# PAGE2.net
KiCad netlist of a schematic drawn in Altium Designer
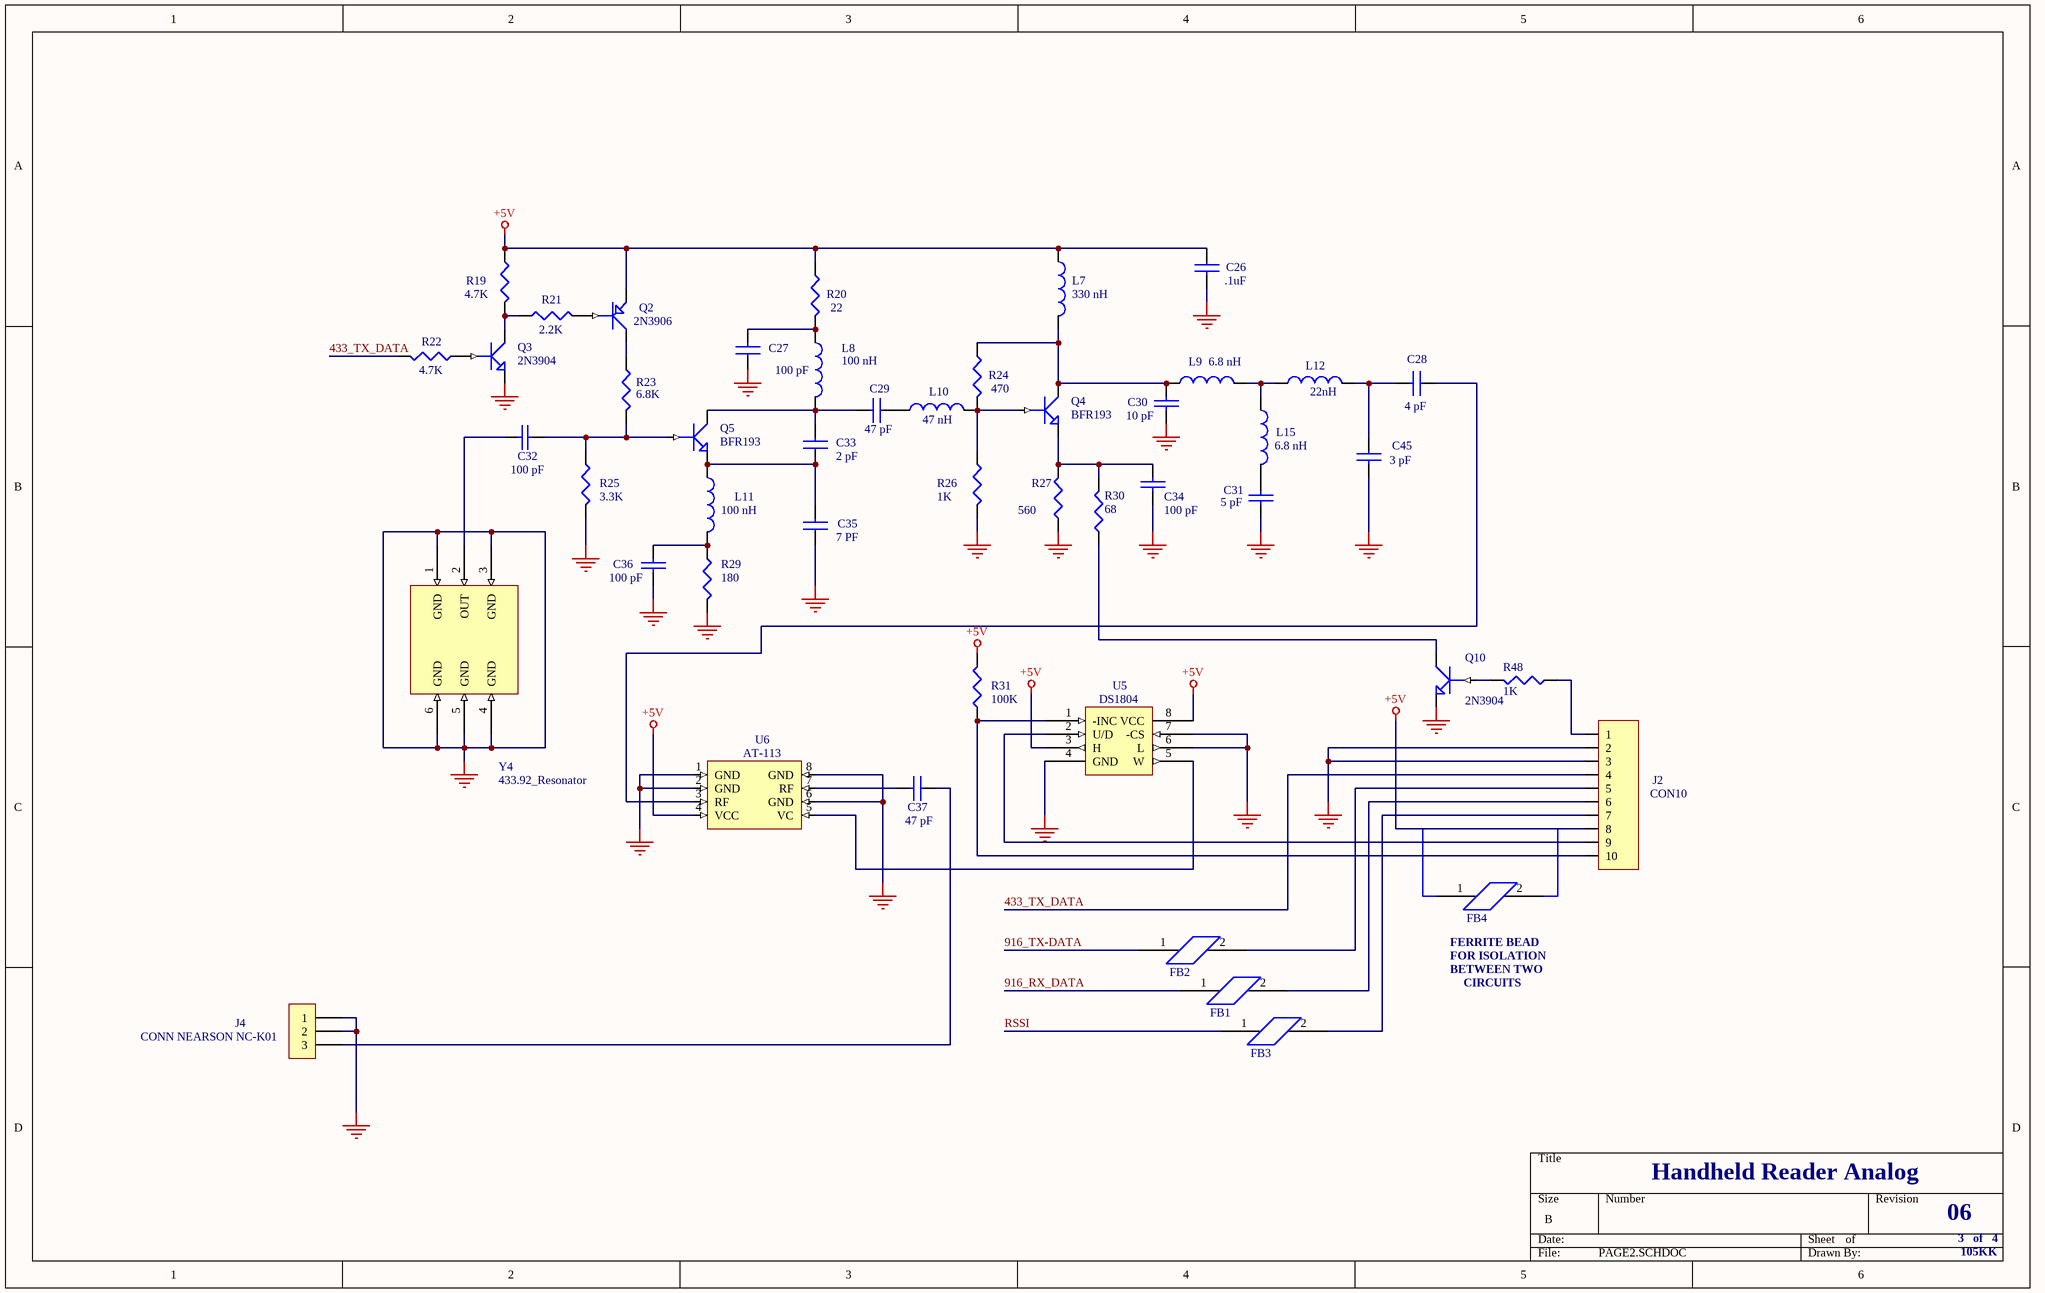
[diagram p0: PAGE2.SCHDOC]

(export (version "E")
  (design (tool "Eeschema 10.0.6"))
  (components
    (comp (ref "C26") (value ".1uF") (footprint "0603") (libsource (lib "*") (part "CAP_NP")))
    (comp (ref "C27") (value "100 pF") (footprint "0603") (libsource (lib "*") (part "CAP_NP")))
    (comp (ref "C28") (value "4 pF") (footprint "0603") (libsource (lib "*") (part "CAP_NP")))
    (comp (ref "C29") (value "47 pF") (footprint "0603") (libsource (lib "*") (part "CAP_NP")))
    (comp (ref "C30")
      (value "10 pF")
      (footprint "0603")
      (description "Capacitor")
      (libsource (lib "*") (part "CAP"))
    )
    (comp (ref "C31")
      (value "5 pF")
      (footprint "0603")
      (description "Capacitor")
      (libsource (lib "*") (part "CAP"))
    )
    (comp (ref "C32")
      (value "100 pF")
      (footprint "0603")
      (description "Capacitor")
      (libsource (lib "*") (part "CAP"))
    )
    (comp (ref "C33") (value "2 pF") (footprint "0603") (libsource (lib "*") (part "CAP_NP")))
    (comp (ref "C34")
      (value "100 pF")
      (footprint "0603")
      (description "Capacitor")
      (libsource (lib "*") (part "CAP"))
    )
    (comp (ref "C35") (value "7 PF") (footprint "0603") (libsource (lib "*") (part "CAP_NP")))
    (comp (ref "C36")
      (value "100 pF")
      (footprint "0603")
      (description "Capacitor")
      (libsource (lib "*") (part "CAP"))
    )
    (comp (ref "C37") (value "47 pF") (footprint "0603") (libsource (lib "*") (part "CAP_NP")))
    (comp (ref "C45") (value "3 pF") (footprint "0603") (libsource (lib "*") (part "CAP_NP")))
    (comp (ref "FB1") (value "FB") (footprint "0603") (libsource (lib "*") (part "FB_0603")))
    (comp (ref "FB2") (value "FB") (footprint "0603") (libsource (lib "*") (part "FB_0603")))
    (comp (ref "FB3") (value "FB") (footprint "0603") (libsource (lib "*") (part "FB_0603")))
    (comp (ref "FB4") (value "FB") (footprint "0603") (libsource (lib "*") (part "FB_0603")))
    (comp (ref "J2") (value "CON10") (footprint "1X10 HEADER") (libsource (lib "*") (part "CON10")))
    (comp (ref "J4")
      (value "CONN NEARSON NC-K01")
      (footprint "CONN NEARSON NC-K01")
      (description "Connector")
      (libsource (lib "*") (part "CON3"))
    )
    (comp (ref "L7") (value "330 nH") (footprint "0805") (libsource (lib "*") (part "INDUCTOR")))
    (comp (ref "L8") (value "100 nH") (footprint "0603") (libsource (lib "*") (part "INDUCTOR")))
    (comp (ref "L9") (value "6.8 nH") (footprint "0603") (libsource (lib "*") (part "INDUCTOR")))
    (comp (ref "L10") (value "47 nH") (footprint "0603") (libsource (lib "*") (part "INDUCTOR")))
    (comp (ref "L11") (value "100 nH") (footprint "0603") (libsource (lib "*") (part "INDUCTOR")))
    (comp (ref "L12") (value "22nH") (footprint "0603") (libsource (lib "*") (part "INDUCTOR")))
    (comp (ref "L15") (value "6.8 nH") (footprint "0603") (libsource (lib "*") (part "INDUCTOR")))
    (comp (ref "Q2")
      (value "2N3906")
      (footprint "SOT23 TRANS")
      (description "PNP Transistor")
      (libsource (lib "*") (part "PNP1"))
    )
    (comp (ref "Q3")
      (value "2N3904")
      (footprint "SOT23 TRANS")
      (description "NPN Transistor")
      (libsource (lib "*") (part "NPN1"))
    )
    (comp (ref "Q4")
      (value "BFR193")
      (footprint "SOT23 TRANS")
      (description "NPN Transistor")
      (libsource (lib "*") (part "NPN1"))
    )
    (comp (ref "Q5")
      (value "BFR193")
      (footprint "SOT23 TRANS")
      (description "NPN Transistor")
      (libsource (lib "*") (part "NPN1"))
    )
    (comp (ref "Q10")
      (value "2N3904")
      (footprint "SOT23 TRANS")
      (description "NPN Transistor")
      (libsource (lib "*") (part "NPN1"))
    )
    (comp (ref "R19") (value "4.7K") (footprint "0603") (libsource (lib "*") (part "RESISTOR")))
    (comp (ref "R20") (value "22") (footprint "0603") (libsource (lib "*") (part "RESISTOR")))
    (comp (ref "R21") (value "2.2K") (footprint "0603") (libsource (lib "*") (part "RESISTOR")))
    (comp (ref "R22") (value "4.7K") (footprint "0603") (libsource (lib "*") (part "RESISTOR")))
    (comp (ref "R23") (value "6.8K") (footprint "0603") (libsource (lib "*") (part "RESISTOR")))
    (comp (ref "R24") (value "470") (footprint "0603") (libsource (lib "*") (part "RESISTOR")))
    (comp (ref "R25") (value "3.3K") (footprint "0603") (libsource (lib "*") (part "RESISTOR")))
    (comp (ref "R26") (value "1K") (footprint "0603") (libsource (lib "*") (part "RESISTOR")))
    (comp (ref "R27") (value "560") (footprint "0603") (libsource (lib "*") (part "RESISTOR")))
    (comp (ref "R29") (value "180") (footprint "0603") (libsource (lib "*") (part "RESISTOR")))
    (comp (ref "R30") (value "68") (footprint "0603") (libsource (lib "*") (part "RESISTOR")))
    (comp (ref "R31") (value "100K") (footprint "0603") (libsource (lib "*") (part "RESISTOR")))
    (comp (ref "R48") (value "1K") (footprint "0603") (libsource (lib "*") (part "RESISTOR")))
    (comp (ref "U5") (value "DS1804") (footprint "SO8 SMALL") (libsource (lib "*") (part "DS1804")))
    (comp (ref "U6") (value "AT-113") (footprint "SO8") (libsource (lib "*") (part "AT-113A")))
    (comp (ref "Y4")
      (value "433.92_Resonator")
      (footprint "RESONATOR2")
      (libsource (lib "*") (part "RESONATOR2"))
    )
  )
  (nets
    (net (code "1") (name "+5V") (class "Default")
      (node (ref "C26") (pin "1") (pinfunction "1_1") (pintype "passive"))
      (node (ref "J2") (pin "8") (pinfunction "8_8") (pintype "passive"))
      (node (ref "L7") (pin "1") (pinfunction "1_1") (pintype "passive"))
      (node (ref "Q2") (pin "E") (pinfunction "E_E") (pintype "passive"))
      (node (ref "R19") (pin "1") (pinfunction "1_1") (pintype "passive"))
      (node (ref "R20") (pin "1") (pinfunction "1_1") (pintype "passive"))
      (node (ref "R31") (pin "1") (pinfunction "1_1") (pintype "passive"))
      (node (ref "U5") (pin "3") (pinfunction "H_3") (pintype "output"))
      (node (ref "U5") (pin "8") (pinfunction "VCC_8") (pintype "power_in"))
      (node (ref "U6") (pin "4") (pinfunction "VCC_4") (pintype "input"))
    )
    (net (code "2") (name "/433_TX_DATA") (class "Default")
      (node (ref "J2") (pin "4") (pinfunction "4_4") (pintype "passive"))
      (node (ref "R22") (pin "2") (pinfunction "2_2") (pintype "passive"))
    )
    (net (code "3") (name "/916_RX_DATA") (class "Default")
      (node (ref "FB1") (pin "1") (pinfunction "2_1") (pintype "passive"))
    )
    (net (code "4") (name "/916_TX-DATA") (class "Default")
      (node (ref "FB2") (pin "1") (pinfunction "2_1") (pintype "passive"))
    )
    (net (code "5") (name "/RSSI") (class "Default")
      (node (ref "FB3") (pin "1") (pinfunction "2_1") (pintype "passive"))
    )
    (net (code "6") (name "GND_SIGNAL") (class "Default")
      (node (ref "C26") (pin "2") (pinfunction "2_2") (pintype "passive"))
      (node (ref "C27") (pin "1") (pinfunction "1_1") (pintype "passive"))
      (node (ref "C30") (pin "2") (pinfunction "2_2") (pintype "passive"))
      (node (ref "C31") (pin "2") (pinfunction "2_2") (pintype "passive"))
      (node (ref "C34") (pin "2") (pinfunction "2_2") (pintype "passive"))
      (node (ref "C35") (pin "1") (pinfunction "1_1") (pintype "passive"))
      (node (ref "C36") (pin "2") (pinfunction "2_2") (pintype "passive"))
      (node (ref "C45") (pin "2") (pinfunction "2_2") (pintype "passive"))
      (node (ref "J2") (pin "2") (pinfunction "2_2") (pintype "passive"))
      (node (ref "J2") (pin "3") (pinfunction "3_3") (pintype "passive"))
      (node (ref "J4") (pin "1") (pinfunction "1_1") (pintype "passive"))
      (node (ref "J4") (pin "2") (pinfunction "2_2") (pintype "passive"))
      (node (ref "Q10") (pin "E") (pinfunction "E_E") (pintype "passive"))
      (node (ref "Q3") (pin "E") (pinfunction "E_E") (pintype "passive"))
      (node (ref "R25") (pin "2") (pinfunction "2_2") (pintype "passive"))
      (node (ref "R26") (pin "2") (pinfunction "2_2") (pintype "passive"))
      (node (ref "R27") (pin "2") (pinfunction "2_2") (pintype "passive"))
      (node (ref "R29") (pin "2") (pinfunction "2_2") (pintype "passive"))
      (node (ref "U5") (pin "4") (pinfunction "GND_4") (pintype "power_in"))
      (node (ref "U5") (pin "6") (pinfunction "L_6") (pintype "output"))
      (node (ref "U5") (pin "7") (pinfunction "-CS_7") (pintype "input"))
      (node (ref "U6") (pin "1") (pinfunction "GND_1") (pintype "input"))
      (node (ref "U6") (pin "2") (pinfunction "GND_2") (pintype "input"))
      (node (ref "U6") (pin "6") (pinfunction "GND_6") (pintype "input"))
      (node (ref "U6") (pin "8") (pinfunction "GND_8") (pintype "input"))
      (node (ref "Y4") (pin "1") (pinfunction "GND_1") (pintype "input"))
      (node (ref "Y4") (pin "3") (pinfunction "GND_3") (pintype "input"))
      (node (ref "Y4") (pin "4") (pinfunction "GND_4") (pintype "input"))
      (node (ref "Y4") (pin "5") (pinfunction "GND_5") (pintype "input"))
      (node (ref "Y4") (pin "6") (pinfunction "GND_6") (pintype "input"))
    )
    (net (code "7") (name "Net-(C27-Pad2)") (class "Default")
      (node (ref "C27") (pin "2") (pinfunction "2_2") (pintype "passive"))
      (node (ref "L8") (pin "1") (pinfunction "1_1") (pintype "passive"))
      (node (ref "R20") (pin "2") (pinfunction "2_2") (pintype "passive"))
    )
    (net (code "8") (name "Net-(C28-Pad1)") (class "Default")
      (node (ref "C28") (pin "1") (pinfunction "1_1") (pintype "passive"))
      (node (ref "U6") (pin "3") (pinfunction "RF_3") (pintype "input"))
    )
    (net (code "9") (name "Net-(C28-Pad2)") (class "Default")
      (node (ref "C28") (pin "2") (pinfunction "2_2") (pintype "passive"))
      (node (ref "C45") (pin "1") (pinfunction "1_1") (pintype "passive"))
      (node (ref "L12") (pin "2") (pinfunction "2_2") (pintype "passive"))
    )
    (net (code "10") (name "Net-(C29-Pad1)") (class "Default")
      (node (ref "C29") (pin "1") (pinfunction "1_1") (pintype "passive"))
      (node (ref "L10") (pin "1") (pinfunction "1_1") (pintype "passive"))
    )
    (net (code "11") (name "Net-(C29-Pad2)") (class "Default")
      (node (ref "C29") (pin "2") (pinfunction "2_2") (pintype "passive"))
      (node (ref "C33") (pin "2") (pinfunction "2_2") (pintype "passive"))
      (node (ref "L8") (pin "2") (pinfunction "2_2") (pintype "passive"))
      (node (ref "Q5") (pin "C") (pinfunction "C_C") (pintype "passive"))
    )
    (net (code "12") (name "Net-(C30-Pad1)") (class "Default")
      (node (ref "C30") (pin "1") (pinfunction "1_1") (pintype "passive"))
      (node (ref "L7") (pin "2") (pinfunction "2_2") (pintype "passive"))
      (node (ref "L9") (pin "1") (pinfunction "1_1") (pintype "passive"))
      (node (ref "Q4") (pin "C") (pinfunction "C_C") (pintype "passive"))
      (node (ref "R24") (pin "1") (pinfunction "1_1") (pintype "passive"))
    )
    (net (code "13") (name "Net-(C31-Pad1)") (class "Default")
      (node (ref "C31") (pin "1") (pinfunction "1_1") (pintype "passive"))
      (node (ref "L15") (pin "2") (pinfunction "2_2") (pintype "passive"))
    )
    (net (code "14") (name "Net-(C32-Pad2)") (class "Default")
      (node (ref "C32") (pin "2") (pinfunction "2_2") (pintype "passive"))
      (node (ref "Q5") (pin "B") (pinfunction "B_B") (pintype "input"))
      (node (ref "R23") (pin "2") (pinfunction "2_2") (pintype "passive"))
      (node (ref "R25") (pin "1") (pinfunction "1_1") (pintype "passive"))
    )
    (net (code "15") (name "Net-(C33-Pad1)") (class "Default")
      (node (ref "C33") (pin "1") (pinfunction "1_1") (pintype "passive"))
      (node (ref "C35") (pin "2") (pinfunction "2_2") (pintype "passive"))
      (node (ref "L11") (pin "1") (pinfunction "1_1") (pintype "passive"))
      (node (ref "Q5") (pin "E") (pinfunction "E_E") (pintype "passive"))
    )
    (net (code "16") (name "Net-(C34-Pad1)") (class "Default")
      (node (ref "C34") (pin "1") (pinfunction "1_1") (pintype "passive"))
      (node (ref "Q4") (pin "E") (pinfunction "E_E") (pintype "passive"))
      (node (ref "R27") (pin "1") (pinfunction "1_1") (pintype "passive"))
      (node (ref "R30") (pin "2") (pinfunction "2_2") (pintype "passive"))
    )
    (net (code "17") (name "Net-(C36-Pad1)") (class "Default")
      (node (ref "C36") (pin "1") (pinfunction "1_1") (pintype "passive"))
      (node (ref "L11") (pin "2") (pinfunction "2_2") (pintype "passive"))
      (node (ref "R29") (pin "1") (pinfunction "1_1") (pintype "passive"))
    )
    (net (code "18") (name "Net-(C37-Pad1)") (class "Default")
      (node (ref "C37") (pin "1") (pinfunction "1_1") (pintype "passive"))
      (node (ref "J4") (pin "3") (pinfunction "3_3") (pintype "passive"))
    )
    (net (code "19") (name "Net-(C37-Pad2)") (class "Default")
      (node (ref "C37") (pin "2") (pinfunction "2_2") (pintype "passive"))
      (node (ref "U6") (pin "7") (pinfunction "RF_7") (pintype "input"))
    )
    (net (code "20") (name "Net-(FB1-1)") (class "Default")
      (node (ref "FB1") (pin "2") (pinfunction "1_2") (pintype "passive"))
      (node (ref "J2") (pin "6") (pinfunction "6_6") (pintype "passive"))
    )
    (net (code "21") (name "Net-(FB2-1)") (class "Default")
      (node (ref "FB2") (pin "2") (pinfunction "1_2") (pintype "passive"))
      (node (ref "J2") (pin "5") (pinfunction "5_5") (pintype "passive"))
    )
    (net (code "22") (name "Net-(FB3-1)") (class "Default")
      (node (ref "FB3") (pin "2") (pinfunction "1_2") (pintype "passive"))
      (node (ref "J2") (pin "7") (pinfunction "7_7") (pintype "passive"))
    )
    (net (code "23") (name "Net-(J2-Pad1)") (class "Default")
      (node (ref "J2") (pin "1") (pinfunction "1_1") (pintype "passive"))
      (node (ref "R48") (pin "2") (pinfunction "2_2") (pintype "passive"))
    )
    (net (code "24") (name "Net-(L10-Pad2)") (class "Default")
      (node (ref "L10") (pin "2") (pinfunction "2_2") (pintype "passive"))
      (node (ref "Q4") (pin "B") (pinfunction "B_B") (pintype "input"))
      (node (ref "R24") (pin "2") (pinfunction "2_2") (pintype "passive"))
      (node (ref "R26") (pin "1") (pinfunction "1_1") (pintype "passive"))
    )
    (net (code "25") (name "Net-(L12-Pad1)") (class "Default")
      (node (ref "L12") (pin "1") (pinfunction "1_1") (pintype "passive"))
      (node (ref "L15") (pin "1") (pinfunction "1_1") (pintype "passive"))
      (node (ref "L9") (pin "2") (pinfunction "2_2") (pintype "passive"))
    )
    (net (code "26") (name "Net-(Q2-PadB)") (class "Default")
      (node (ref "Q2") (pin "B") (pinfunction "B_B") (pintype "input"))
      (node (ref "R21") (pin "2") (pinfunction "2_2") (pintype "passive"))
    )
    (net (code "27") (name "Net-(Q2-PadC)") (class "Default")
      (node (ref "Q2") (pin "C") (pinfunction "C_C") (pintype "passive"))
      (node (ref "R23") (pin "1") (pinfunction "1_1") (pintype "passive"))
    )
    (net (code "28") (name "Net-(Q3-PadB)") (class "Default")
      (node (ref "Q3") (pin "B") (pinfunction "B_B") (pintype "input"))
      (node (ref "R22") (pin "1") (pinfunction "1_1") (pintype "passive"))
    )
    (net (code "29") (name "Net-(Q3-PadC)") (class "Default")
      (node (ref "Q3") (pin "C") (pinfunction "C_C") (pintype "passive"))
      (node (ref "R19") (pin "2") (pinfunction "2_2") (pintype "passive"))
      (node (ref "R21") (pin "1") (pinfunction "1_1") (pintype "passive"))
    )
    (net (code "30") (name "Net-(Q10-PadB)") (class "Default")
      (node (ref "Q10") (pin "B") (pinfunction "B_B") (pintype "input"))
      (node (ref "R48") (pin "1") (pinfunction "1_1") (pintype "passive"))
    )
    (net (code "31") (name "Net-(Q10-PadC)") (class "Default")
      (node (ref "Q10") (pin "C") (pinfunction "C_C") (pintype "passive"))
      (node (ref "R30") (pin "1") (pinfunction "1_1") (pintype "passive"))
    )
    (net (code "32") (name "Net-(U5--INC)") (class "Default")
      (node (ref "J2") (pin "10") (pinfunction "10_10") (pintype "passive"))
      (node (ref "R31") (pin "2") (pinfunction "2_2") (pintype "passive"))
      (node (ref "U5") (pin "1") (pinfunction "-INC_1") (pintype "input"))
    )
    (net (code "33") (name "Net-(U5-U{slash}D)") (class "Default")
      (node (ref "J2") (pin "9") (pinfunction "9_9") (pintype "passive"))
      (node (ref "U5") (pin "2") (pinfunction "U/D_2") (pintype "input"))
    )
    (net (code "34") (name "Net-(U5-W)") (class "Default")
      (node (ref "U5") (pin "5") (pinfunction "W_5") (pintype "output"))
      (node (ref "U6") (pin "5") (pinfunction "VC_5") (pintype "input"))
    )
    (net (code "35") (name "Net-(Y4-OUT)") (class "Default")
      (node (ref "C32") (pin "1") (pinfunction "1_1") (pintype "passive"))
      (node (ref "Y4") (pin "2") (pinfunction "OUT_2") (pintype "input"))
    )
    (net (code "36") (name "unconnected-(FB4-1-Pad2)") (class "Default")
      (node (ref "FB4") (pin "2") (pinfunction "1_2") (pintype "passive"))
    )
    (net (code "37") (name "unconnected-(FB4-2-Pad1)") (class "Default")
      (node (ref "FB4") (pin "1") (pinfunction "2_1") (pintype "passive"))
    )
  )
)
